# shield.net
KiCad netlist of a schematic drawn in EAGLE
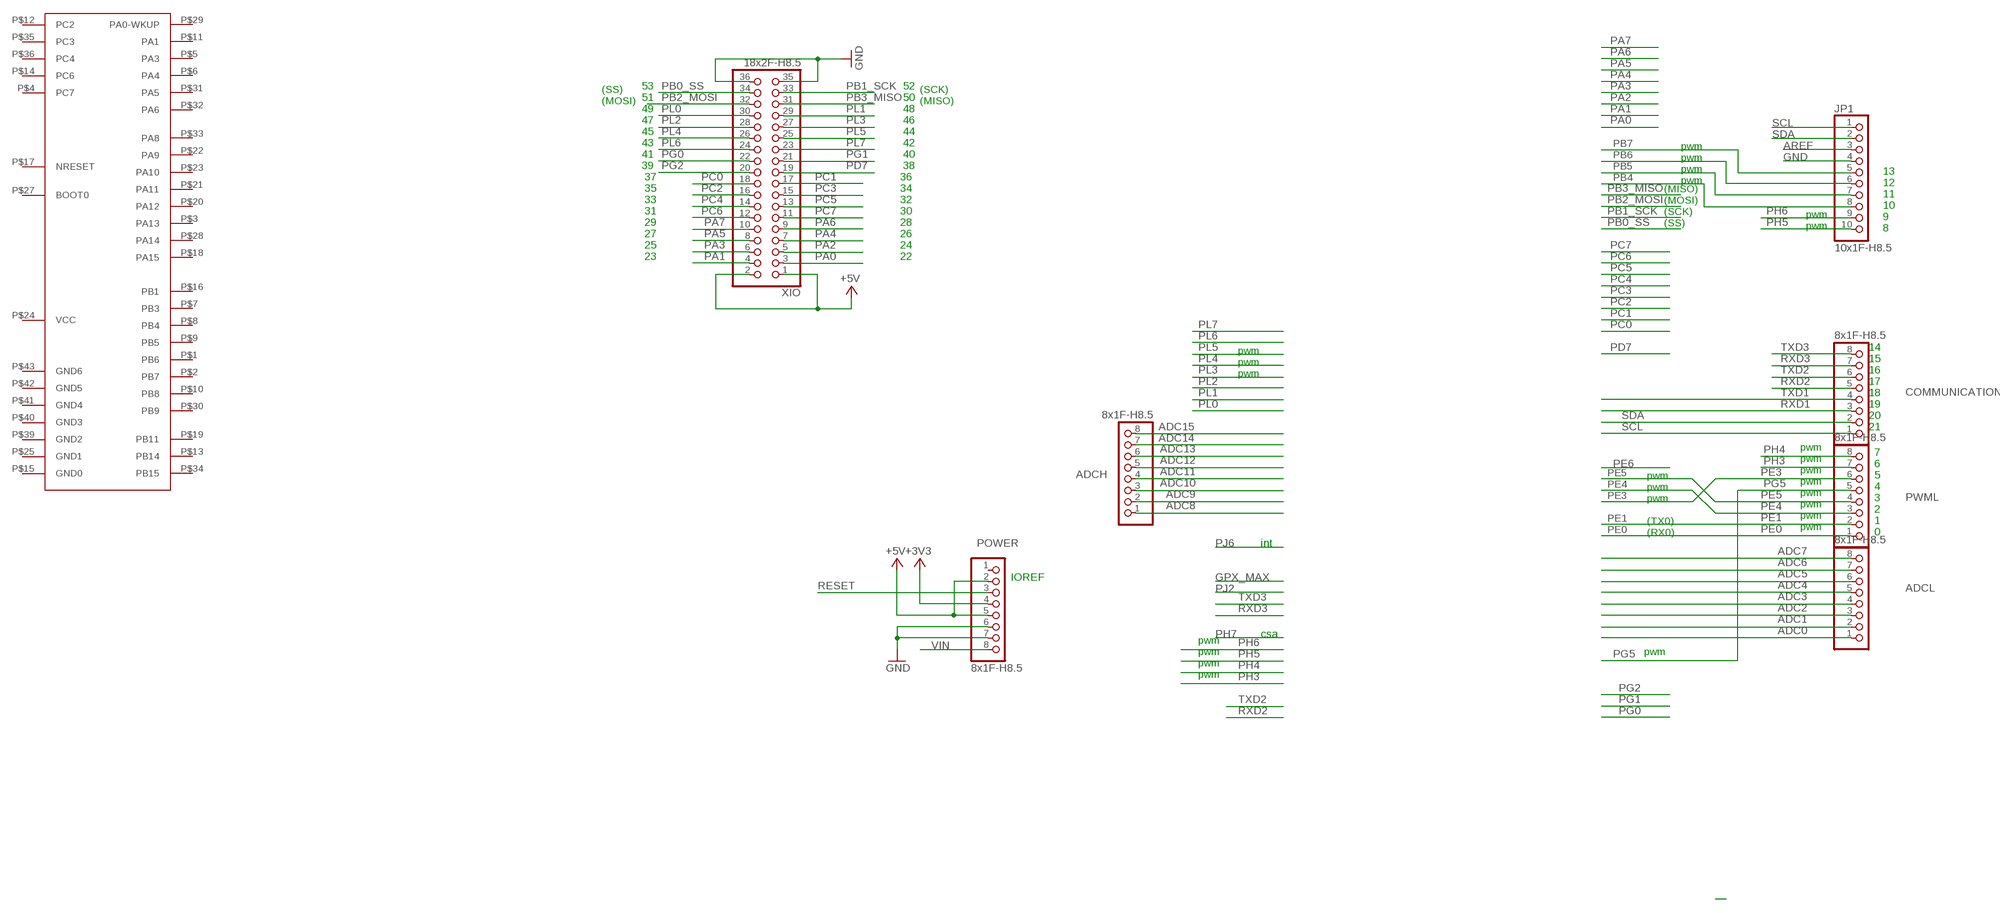
[diagram p0: schematic, sheet 1]

(export (version "E")
  (design (tool "Eeschema 10.0.6"))
  (components
    (comp (ref "ADCH")
      (value "8x1F-H8.5")
      (footprint "eagle-import:1X08")
      (libsource (lib "eagle-import") (part "PINHD-1X8"))
    )
    (comp (ref "ADCL")
      (value "8x1F-H8.5")
      (footprint "eagle-import:1X08")
      (libsource (lib "eagle-import") (part "PINHD-1X8"))
    )
    (comp (ref "COMMUNICATION")
      (value "8x1F-H8.5")
      (footprint "eagle-import:1X08")
      (libsource (lib "eagle-import") (part "PINHD-1X8"))
    )
    (comp (ref "JP1")
      (value "10x1F-H8.5")
      (footprint "eagle-import:1X10")
      (libsource (lib "eagle-import") (part "PINHD-1X10"))
    )
    (comp (ref "POWER")
      (value "8x1F-H8.5")
      (footprint "eagle-import:1X08")
      (libsource (lib "eagle-import") (part "PINHD-1X8"))
    )
    (comp (ref "PWML")
      (value "8x1F-H8.5")
      (footprint "eagle-import:1X08")
      (libsource (lib "eagle-import") (part "PINHD-1X8"))
    )
    (comp (ref "U$1")
      (value "EMW3162")
      (footprint "eagle-import:EMW3162")
      (libsource (lib "eagle-import") (part "EMW3162"))
    )
    (comp (ref "XIO")
      (value "18x2F-H8.5")
      (footprint "eagle-import:2X18")
      (libsource (lib "eagle-import") (part "PINHD-2X18"))
    )
  )
  (nets
    (net (code "1") (name "+3V3") (class "Default")
      (node (ref "POWER") (pin "4") (pinfunction "4_4") (pintype "passive"))
    )
    (net (code "2") (name "+5V") (class "Default")
      (node (ref "POWER") (pin "2") (pinfunction "2_2") (pintype "passive"))
      (node (ref "POWER") (pin "5") (pinfunction "5_5") (pintype "passive"))
      (node (ref "XIO") (pin "1") (pinfunction "1_1") (pintype "passive"))
      (node (ref "XIO") (pin "2") (pinfunction "2_2") (pintype "passive"))
    )
    (net (code "3") (name "/ADC0") (class "Default")
      (node (ref "ADCL") (pin "1") (pinfunction "1_1") (pintype "passive"))
    )
    (net (code "4") (name "/ADC1") (class "Default")
      (node (ref "ADCL") (pin "2") (pinfunction "2_2") (pintype "passive"))
    )
    (net (code "5") (name "/ADC2") (class "Default")
      (node (ref "ADCL") (pin "3") (pinfunction "3_3") (pintype "passive"))
    )
    (net (code "6") (name "/ADC3") (class "Default")
      (node (ref "ADCL") (pin "4") (pinfunction "4_4") (pintype "passive"))
    )
    (net (code "7") (name "/ADC4") (class "Default")
      (node (ref "ADCL") (pin "5") (pinfunction "5_5") (pintype "passive"))
    )
    (net (code "8") (name "/ADC5") (class "Default")
      (node (ref "ADCL") (pin "6") (pinfunction "6_6") (pintype "passive"))
    )
    (net (code "9") (name "/ADC6") (class "Default")
      (node (ref "ADCL") (pin "7") (pinfunction "7_7") (pintype "passive"))
    )
    (net (code "10") (name "/ADC7") (class "Default")
      (node (ref "ADCL") (pin "8") (pinfunction "8_8") (pintype "passive"))
    )
    (net (code "11") (name "/ADC8") (class "Default")
      (node (ref "ADCH") (pin "1") (pinfunction "1_1") (pintype "passive"))
    )
    (net (code "12") (name "/ADC9") (class "Default")
      (node (ref "ADCH") (pin "2") (pinfunction "2_2") (pintype "passive"))
    )
    (net (code "13") (name "/ADC10") (class "Default")
      (node (ref "ADCH") (pin "3") (pinfunction "3_3") (pintype "passive"))
    )
    (net (code "14") (name "/ADC11") (class "Default")
      (node (ref "ADCH") (pin "4") (pinfunction "4_4") (pintype "passive"))
    )
    (net (code "15") (name "/ADC12") (class "Default")
      (node (ref "ADCH") (pin "5") (pinfunction "5_5") (pintype "passive"))
    )
    (net (code "16") (name "/ADC13") (class "Default")
      (node (ref "ADCH") (pin "6") (pinfunction "6_6") (pintype "passive"))
    )
    (net (code "17") (name "/ADC14") (class "Default")
      (node (ref "ADCH") (pin "7") (pinfunction "7_7") (pintype "passive"))
    )
    (net (code "18") (name "/ADC15") (class "Default")
      (node (ref "ADCH") (pin "8") (pinfunction "8_8") (pintype "passive"))
    )
    (net (code "19") (name "/AREF") (class "Default")
      (node (ref "JP1") (pin "3") (pinfunction "3_3") (pintype "passive"))
    )
    (net (code "21") (name "/PA0") (class "Default")
      (node (ref "XIO") (pin "3") (pinfunction "3_3") (pintype "passive"))
    )
    (net (code "22") (name "/PA1") (class "Default")
      (node (ref "XIO") (pin "4") (pinfunction "4_4") (pintype "passive"))
    )
    (net (code "23") (name "/PA2") (class "Default")
      (node (ref "XIO") (pin "5") (pinfunction "5_5") (pintype "passive"))
    )
    (net (code "24") (name "/PA3") (class "Default")
      (node (ref "XIO") (pin "6") (pinfunction "6_6") (pintype "passive"))
    )
    (net (code "25") (name "/PA4") (class "Default")
      (node (ref "XIO") (pin "7") (pinfunction "7_7") (pintype "passive"))
    )
    (net (code "26") (name "/PA5") (class "Default")
      (node (ref "XIO") (pin "8") (pinfunction "8_8") (pintype "passive"))
    )
    (net (code "27") (name "/PA6") (class "Default")
      (node (ref "XIO") (pin "9") (pinfunction "9_9") (pintype "passive"))
    )
    (net (code "28") (name "/PA7") (class "Default")
      (node (ref "XIO") (pin "10") (pinfunction "10_10") (pintype "passive"))
    )
    (net (code "29") (name "/PB0_SS") (class "Default")
      (node (ref "XIO") (pin "34") (pinfunction "34_34") (pintype "passive"))
    )
    (net (code "30") (name "/PB1_SCK") (class "Default")
      (node (ref "XIO") (pin "33") (pinfunction "33_33") (pintype "passive"))
    )
    (net (code "31") (name "/PB2_MOSI") (class "Default")
      (node (ref "XIO") (pin "32") (pinfunction "32_32") (pintype "passive"))
    )
    (net (code "32") (name "/PB3_MISO") (class "Default")
      (node (ref "XIO") (pin "31") (pinfunction "31_31") (pintype "passive"))
    )
    (net (code "33") (name "/PB4") (class "Default")
      (node (ref "JP1") (pin "8") (pinfunction "8_8") (pintype "passive"))
    )
    (net (code "34") (name "/PB5") (class "Default")
      (node (ref "JP1") (pin "7") (pinfunction "7_7") (pintype "passive"))
    )
    (net (code "35") (name "/PB6") (class "Default")
      (node (ref "JP1") (pin "6") (pinfunction "6_6") (pintype "passive"))
    )
    (net (code "36") (name "/PB7") (class "Default")
      (node (ref "JP1") (pin "5") (pinfunction "5_5") (pintype "passive"))
    )
    (net (code "37") (name "/PC0") (class "Default")
      (node (ref "XIO") (pin "18") (pinfunction "18_18") (pintype "passive"))
    )
    (net (code "38") (name "/PC1") (class "Default")
      (node (ref "XIO") (pin "17") (pinfunction "17_17") (pintype "passive"))
    )
    (net (code "39") (name "/PC2") (class "Default")
      (node (ref "XIO") (pin "16") (pinfunction "16_16") (pintype "passive"))
    )
    (net (code "40") (name "/PC3") (class "Default")
      (node (ref "XIO") (pin "15") (pinfunction "15_15") (pintype "passive"))
    )
    (net (code "41") (name "/PC4") (class "Default")
      (node (ref "XIO") (pin "14") (pinfunction "14_14") (pintype "passive"))
    )
    (net (code "42") (name "/PC5") (class "Default")
      (node (ref "XIO") (pin "13") (pinfunction "13_13") (pintype "passive"))
    )
    (net (code "43") (name "/PC6") (class "Default")
      (node (ref "XIO") (pin "12") (pinfunction "12_12") (pintype "passive"))
    )
    (net (code "44") (name "/PC7") (class "Default")
      (node (ref "XIO") (pin "11") (pinfunction "11_11") (pintype "passive"))
    )
    (net (code "45") (name "/PD7") (class "Default")
      (node (ref "XIO") (pin "19") (pinfunction "19_19") (pintype "passive"))
    )
    (net (code "46") (name "/PE0") (class "Default")
      (node (ref "PWML") (pin "1") (pinfunction "1_1") (pintype "passive"))
    )
    (net (code "47") (name "/PE1") (class "Default")
      (node (ref "PWML") (pin "2") (pinfunction "2_2") (pintype "passive"))
    )
    (net (code "48") (name "/PE3") (class "Default")
      (node (ref "PWML") (pin "6") (pinfunction "6_6") (pintype "passive"))
    )
    (net (code "49") (name "/PE4") (class "Default")
      (node (ref "PWML") (pin "3") (pinfunction "3_3") (pintype "passive"))
    )
    (net (code "50") (name "/PE5") (class "Default")
      (node (ref "PWML") (pin "4") (pinfunction "4_4") (pintype "passive"))
    )
    (net (code "52") (name "/PG0") (class "Default")
      (node (ref "XIO") (pin "22") (pinfunction "22_22") (pintype "passive"))
    )
    (net (code "53") (name "/PG1") (class "Default")
      (node (ref "XIO") (pin "21") (pinfunction "21_21") (pintype "passive"))
    )
    (net (code "54") (name "/PG2") (class "Default")
      (node (ref "XIO") (pin "20") (pinfunction "20_20") (pintype "passive"))
    )
    (net (code "55") (name "/PG5") (class "Default")
      (node (ref "PWML") (pin "5") (pinfunction "5_5") (pintype "passive"))
    )
    (net (code "56") (name "/PH3") (class "Default")
      (node (ref "PWML") (pin "7") (pinfunction "7_7") (pintype "passive"))
    )
    (net (code "57") (name "/PH4") (class "Default")
      (node (ref "PWML") (pin "8") (pinfunction "8_8") (pintype "passive"))
    )
    (net (code "58") (name "/PH5") (class "Default")
      (node (ref "JP1") (pin "10") (pinfunction "10_10") (pintype "passive"))
    )
    (net (code "59") (name "/PH6") (class "Default")
      (node (ref "JP1") (pin "9") (pinfunction "9_9") (pintype "passive"))
    )
    (net (code "63") (name "/PL0") (class "Default")
      (node (ref "XIO") (pin "30") (pinfunction "30_30") (pintype "passive"))
    )
    (net (code "64") (name "/PL1") (class "Default")
      (node (ref "XIO") (pin "29") (pinfunction "29_29") (pintype "passive"))
    )
    (net (code "65") (name "/PL2") (class "Default")
      (node (ref "XIO") (pin "28") (pinfunction "28_28") (pintype "passive"))
    )
    (net (code "66") (name "/PL3") (class "Default")
      (node (ref "XIO") (pin "27") (pinfunction "27_27") (pintype "passive"))
    )
    (net (code "67") (name "/PL4") (class "Default")
      (node (ref "XIO") (pin "26") (pinfunction "26_26") (pintype "passive"))
    )
    (net (code "68") (name "/PL5") (class "Default")
      (node (ref "XIO") (pin "25") (pinfunction "25_25") (pintype "passive"))
    )
    (net (code "69") (name "/PL6") (class "Default")
      (node (ref "XIO") (pin "24") (pinfunction "24_24") (pintype "passive"))
    )
    (net (code "70") (name "/PL7") (class "Default")
      (node (ref "XIO") (pin "23") (pinfunction "23_23") (pintype "passive"))
    )
    (net (code "71") (name "/RESET") (class "Default")
      (node (ref "POWER") (pin "3") (pinfunction "3_3") (pintype "passive"))
    )
    (net (code "72") (name "/RXD1") (class "Default")
      (node (ref "COMMUNICATION") (pin "3") (pinfunction "3_3") (pintype "passive"))
    )
    (net (code "73") (name "/RXD2") (class "Default")
      (node (ref "COMMUNICATION") (pin "5") (pinfunction "5_5") (pintype "passive"))
    )
    (net (code "74") (name "/RXD3") (class "Default")
      (node (ref "COMMUNICATION") (pin "7") (pinfunction "7_7") (pintype "passive"))
    )
    (net (code "75") (name "/SCL") (class "Default")
      (node (ref "COMMUNICATION") (pin "1") (pinfunction "1_1") (pintype "passive"))
      (node (ref "JP1") (pin "1") (pinfunction "1_1") (pintype "passive"))
    )
    (net (code "76") (name "/SDA") (class "Default")
      (node (ref "COMMUNICATION") (pin "2") (pinfunction "2_2") (pintype "passive"))
      (node (ref "JP1") (pin "2") (pinfunction "2_2") (pintype "passive"))
    )
    (net (code "77") (name "/TXD1") (class "Default")
      (node (ref "COMMUNICATION") (pin "4") (pinfunction "4_4") (pintype "passive"))
    )
    (net (code "78") (name "/TXD2") (class "Default")
      (node (ref "COMMUNICATION") (pin "6") (pinfunction "6_6") (pintype "passive"))
    )
    (net (code "79") (name "/TXD3") (class "Default")
      (node (ref "COMMUNICATION") (pin "8") (pinfunction "8_8") (pintype "passive"))
    )
    (net (code "80") (name "/VIN") (class "Default")
      (node (ref "POWER") (pin "8") (pinfunction "8_8") (pintype "passive"))
    )
    (net (code "81") (name "GND") (class "Default")
      (node (ref "JP1") (pin "4") (pinfunction "4_4") (pintype "passive"))
      (node (ref "POWER") (pin "6") (pinfunction "6_6") (pintype "passive"))
      (node (ref "POWER") (pin "7") (pinfunction "7_7") (pintype "passive"))
      (node (ref "XIO") (pin "35") (pinfunction "35_35") (pintype "passive"))
      (node (ref "XIO") (pin "36") (pinfunction "36_36") (pintype "passive"))
    )
    (net (code "82") (name "unconnected-(POWER-Pad1)") (class "Default")
      (node (ref "POWER") (pin "1") (pinfunction "1_1") (pintype "passive"))
    )
    (net (code "83") (name "unconnected-(U$1-BOOT0-PadP$27)") (class "Default")
      (node (ref "U$1") (pin "P$27") (pinfunction "BOOT0_P$27") (pintype "input"))
    )
    (net (code "84") (name "unconnected-(U$1-GND0-PadP$15)") (class "Default")
      (node (ref "U$1") (pin "P$15") (pinfunction "GND0_P$15") (pintype "bidirectional"))
    )
    (net (code "85") (name "unconnected-(U$1-GND1-PadP$25)") (class "Default")
      (node (ref "U$1") (pin "P$25") (pinfunction "GND1_P$25") (pintype "bidirectional"))
    )
    (net (code "86") (name "unconnected-(U$1-GND2-PadP$39)") (class "Default")
      (node (ref "U$1") (pin "P$39") (pinfunction "GND2_P$39") (pintype "bidirectional"))
    )
    (net (code "87") (name "unconnected-(U$1-GND3-PadP$40)") (class "Default")
      (node (ref "U$1") (pin "P$40") (pinfunction "GND3_P$40") (pintype "bidirectional"))
    )
    (net (code "88") (name "unconnected-(U$1-GND4-PadP$41)") (class "Default")
      (node (ref "U$1") (pin "P$41") (pinfunction "GND4_P$41") (pintype "bidirectional"))
    )
    (net (code "89") (name "unconnected-(U$1-GND5-PadP$42)") (class "Default")
      (node (ref "U$1") (pin "P$42") (pinfunction "GND5_P$42") (pintype "bidirectional"))
    )
    (net (code "90") (name "unconnected-(U$1-GND6-PadP$43)") (class "Default")
      (node (ref "U$1") (pin "P$43") (pinfunction "GND6_P$43") (pintype "bidirectional"))
    )
    (net (code "91") (name "unconnected-(U$1-NRESET-PadP$17)") (class "Default")
      (node (ref "U$1") (pin "P$17") (pinfunction "NRESET_P$17") (pintype "bidirectional"))
    )
    (net (code "92") (name "unconnected-(U$1-PA0-WKUP-PadP$29)") (class "Default")
      (node (ref "U$1") (pin "P$29") (pinfunction "PA0-WKUP_P$29") (pintype "bidirectional"))
    )
    (net (code "93") (name "unconnected-(U$1-PA1-PadP$11)") (class "Default")
      (node (ref "U$1") (pin "P$11") (pinfunction "PA1_P$11") (pintype "bidirectional"))
    )
    (net (code "94") (name "unconnected-(U$1-PA3-PadP$5)") (class "Default")
      (node (ref "U$1") (pin "P$5") (pinfunction "PA3_P$5") (pintype "bidirectional"))
    )
    (net (code "95") (name "unconnected-(U$1-PA4-PadP$6)") (class "Default")
      (node (ref "U$1") (pin "P$6") (pinfunction "PA4_P$6") (pintype "bidirectional"))
    )
    (net (code "96") (name "unconnected-(U$1-PA5-PadP$31)") (class "Default")
      (node (ref "U$1") (pin "P$31") (pinfunction "PA5_P$31") (pintype "bidirectional"))
    )
    (net (code "97") (name "unconnected-(U$1-PA6-PadP$32)") (class "Default")
      (node (ref "U$1") (pin "P$32") (pinfunction "PA6_P$32") (pintype "bidirectional"))
    )
    (net (code "98") (name "unconnected-(U$1-PA8-PadP$33)") (class "Default")
      (node (ref "U$1") (pin "P$33") (pinfunction "PA8_P$33") (pintype "bidirectional"))
    )
    (net (code "99") (name "unconnected-(U$1-PA9-PadP$22)") (class "Default")
      (node (ref "U$1") (pin "P$22") (pinfunction "PA9_P$22") (pintype "bidirectional"))
    )
    (net (code "100") (name "unconnected-(U$1-PA10-PadP$23)") (class "Default")
      (node (ref "U$1") (pin "P$23") (pinfunction "PA10_P$23") (pintype "bidirectional"))
    )
    (net (code "101") (name "unconnected-(U$1-PA11-PadP$21)") (class "Default")
      (node (ref "U$1") (pin "P$21") (pinfunction "PA11_P$21") (pintype "bidirectional"))
    )
    (net (code "102") (name "unconnected-(U$1-PA12-PadP$20)") (class "Default")
      (node (ref "U$1") (pin "P$20") (pinfunction "PA12_P$20") (pintype "bidirectional"))
    )
    (net (code "103") (name "unconnected-(U$1-PA13-PadP$3)") (class "Default")
      (node (ref "U$1") (pin "P$3") (pinfunction "PA13_P$3") (pintype "bidirectional"))
    )
    (net (code "104") (name "unconnected-(U$1-PA14-PadP$28)") (class "Default")
      (node (ref "U$1") (pin "P$28") (pinfunction "PA14_P$28") (pintype "bidirectional"))
    )
    (net (code "105") (name "unconnected-(U$1-PA15-PadP$18)") (class "Default")
      (node (ref "U$1") (pin "P$18") (pinfunction "PA15_P$18") (pintype "bidirectional"))
    )
    (net (code "106") (name "unconnected-(U$1-PB1-PadP$16)") (class "Default")
      (node (ref "U$1") (pin "P$16") (pinfunction "PB1_P$16") (pintype "bidirectional"))
    )
    (net (code "107") (name "unconnected-(U$1-PB3-PadP$7)") (class "Default")
      (node (ref "U$1") (pin "P$7") (pinfunction "PB3_P$7") (pintype "bidirectional"))
    )
    (net (code "108") (name "unconnected-(U$1-PB4-PadP$8)") (class "Default")
      (node (ref "U$1") (pin "P$8") (pinfunction "PB4_P$8") (pintype "bidirectional"))
    )
    (net (code "109") (name "unconnected-(U$1-PB5-PadP$9)") (class "Default")
      (node (ref "U$1") (pin "P$9") (pinfunction "PB5_P$9") (pintype "bidirectional"))
    )
    (net (code "110") (name "unconnected-(U$1-PB6-PadP$1)") (class "Default")
      (node (ref "U$1") (pin "P$1") (pinfunction "PB6_P$1") (pintype "bidirectional"))
    )
    (net (code "111") (name "unconnected-(U$1-PB7-PadP$2)") (class "Default")
      (node (ref "U$1") (pin "P$2") (pinfunction "PB7_P$2") (pintype "bidirectional"))
    )
    (net (code "112") (name "unconnected-(U$1-PB8-PadP$10)") (class "Default")
      (node (ref "U$1") (pin "P$10") (pinfunction "PB8_P$10") (pintype "bidirectional"))
    )
    (net (code "113") (name "unconnected-(U$1-PB9-PadP$30)") (class "Default")
      (node (ref "U$1") (pin "P$30") (pinfunction "PB9_P$30") (pintype "bidirectional"))
    )
    (net (code "114") (name "unconnected-(U$1-PB11-PadP$19)") (class "Default")
      (node (ref "U$1") (pin "P$19") (pinfunction "PB11_P$19") (pintype "bidirectional"))
    )
    (net (code "115") (name "unconnected-(U$1-PB14-PadP$13)") (class "Default")
      (node (ref "U$1") (pin "P$13") (pinfunction "PB14_P$13") (pintype "bidirectional"))
    )
    (net (code "116") (name "unconnected-(U$1-PB15-PadP$34)") (class "Default")
      (node (ref "U$1") (pin "P$34") (pinfunction "PB15_P$34") (pintype "bidirectional"))
    )
    (net (code "117") (name "unconnected-(U$1-PC2-PadP$12)") (class "Default")
      (node (ref "U$1") (pin "P$12") (pinfunction "PC2_P$12") (pintype "bidirectional"))
    )
    (net (code "118") (name "unconnected-(U$1-PC3-PadP$35)") (class "Default")
      (node (ref "U$1") (pin "P$35") (pinfunction "PC3_P$35") (pintype "bidirectional"))
    )
    (net (code "119") (name "unconnected-(U$1-PC4-PadP$36)") (class "Default")
      (node (ref "U$1") (pin "P$36") (pinfunction "PC4_P$36") (pintype "bidirectional"))
    )
    (net (code "120") (name "unconnected-(U$1-PC6-PadP$14)") (class "Default")
      (node (ref "U$1") (pin "P$14") (pinfunction "PC6_P$14") (pintype "bidirectional"))
    )
    (net (code "121") (name "unconnected-(U$1-PC7-PadP$4)") (class "Default")
      (node (ref "U$1") (pin "P$4") (pinfunction "PC7_P$4") (pintype "bidirectional"))
    )
    (net (code "122") (name "unconnected-(U$1-VCC-PadP$24)") (class "Default")
      (node (ref "U$1") (pin "P$24") (pinfunction "VCC_P$24") (pintype "bidirectional"))
    )
  )
)
